# PX4FMUv2_4_6_6.net
KiCad netlist of a schematic drawn in Altium Designer
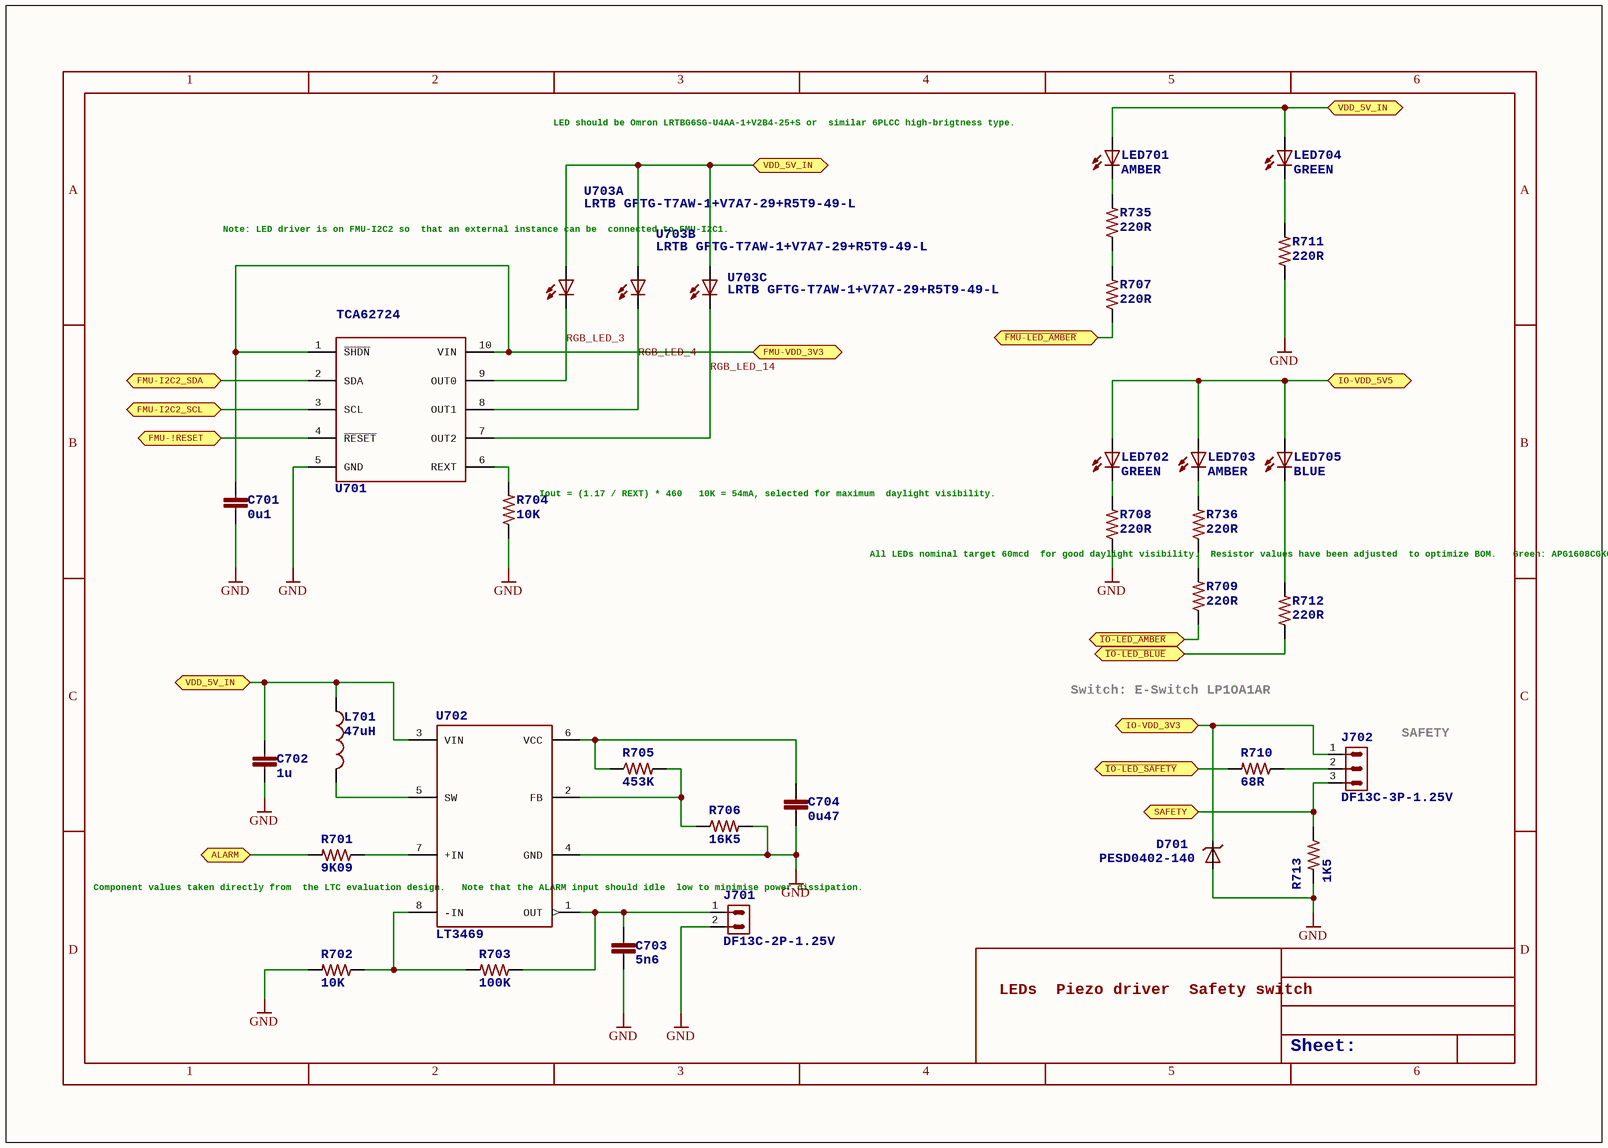
[diagram p0: PX4FMUv2.4.6_6.SchDoc]

(export (version "E")
  (design (tool "Eeschema 10.0.6"))
  (components
    (comp (ref "C701")
      (value "0u1")
      (footprint "0402-CAP")
      (description "CapacitorStandard 0603 ceramic capacitor, and 0.1\" leaded capacitor.")
      (fields (field (name "PARTNO") "CC0402ZRY5V7BB104"))
      (libsource (lib "pixhawk2") (part "CAP0402"))
    )
    (comp (ref "C702")
      (value "1u")
      (footprint "0603-CAP")
      (description "CapacitorStandard 0603 ceramic capacitor, and 0.1\" leaded capacitor.")
      (fields (field (name "PARTNO") "CC0603ZRY5V7BB105"))
      (libsource (lib "pixhawk2") (part "CAP0603"))
    )
    (comp (ref "C703")
      (value "5n6")
      (footprint "0402-CAP")
      (description "CapacitorStandard 0603 ceramic capacitor, and 0.1\" leaded capacitor.")
      (fields (field (name "PARTNO") "C0402C562K5RACTU"))
      (libsource (lib "pixhawk2") (part "CAP0402"))
    )
    (comp (ref "C704")
      (value "0u47")
      (footprint "0402-CAP")
      (description "CapacitorStandard 0603 ceramic capacitor, and 0.1\" leaded capacitor.")
      (fields (field (name "PARTNO") "C1005X5R1C474K050BC"))
      (libsource (lib "pixhawk2") (part "CAP0402"))
    )
    (comp (ref "D701")
      (value "PESD0402-140")
      (footprint "0402-TVS")
      (libsource (lib "pixhawk2") (part "DIODE-TVS"))
    )
    (comp (ref "J701")
      (value "DF13C-2P-1.25V")
      (footprint "DF13C-2P-1.25V")
      (description "DF13-2P 1.25mm Pitch Miniature Crimping Connector.")
      (fields (field (name "PARTNO") "DF13C-2P-1.25V(20)"))
      (libsource (lib "con-hirose-df13") (part "DF13-2P-1.25V"))
    )
    (comp (ref "J702")
      (value "DF13C-3P-1.25V")
      (footprint "DF13C-3P-1.25V")
      (description "DF13-3P 1.25mm Pitch Miniature Crimping Connector.")
      (fields (field (name "PARTNO") "DF13C-3P-1.25V(20)"))
      (libsource (lib "con-hirose-df13") (part "DF13-3P-1.25V"))
    )
    (comp (ref "L701")
      (value "47uH")
      (footprint "0805-IND")
      (fields (field (name "PARTNO") "MLZ2012M470W"))
      (libsource (lib "pixhawk2") (part "INDUCTOR0805"))
    )
    (comp (ref "LED701")
      (value "AMBER")
      (footprint "0603-LED")
      (fields (field (name "PARTNO") "APTD1608SECK"))
      (libsource (lib "pixhawk2") (part "LED0603"))
    )
    (comp (ref "LED702")
      (value "GREEN")
      (footprint "0603-LED")
      (fields (field (name "PARTNO") "APTD1608CGCK"))
      (libsource (lib "pixhawk2") (part "LED0603"))
    )
    (comp (ref "LED703")
      (value "AMBER")
      (footprint "0603-LED")
      (fields (field (name "PARTNO") "APTD1608SECK"))
      (libsource (lib "pixhawk2") (part "LED0603"))
    )
    (comp (ref "LED704")
      (value "GREEN")
      (footprint "0603-LED")
      (fields (field (name "PARTNO") "APTD1608CGCK"))
      (libsource (lib "pixhawk2") (part "LED0603"))
    )
    (comp (ref "LED705")
      (value "BLUE")
      (footprint "0603-LED")
      (fields (field (name "PARTNO") "APTD1608QBC/D"))
      (libsource (lib "pixhawk2") (part "LED0603"))
    )
    (comp (ref "R701")
      (value "9K09")
      (footprint "0402-RES")
      (fields (field (name "PARTNO") "RMCF0402FT9K09"))
      (libsource (lib "pixhawk2") (part "RESISTOR0402-RES"))
    )
    (comp (ref "R702")
      (value "10K")
      (footprint "0402-RES")
      (fields (field (name "PARTNO") "RC0402FR-0710KL"))
      (libsource (lib "pixhawk2") (part "RESISTOR0402-RES"))
    )
    (comp (ref "R703")
      (value "100K")
      (footprint "0402-RES")
      (fields (field (name "PARTNO") "RC0402FR-07100KL"))
      (libsource (lib "pixhawk2") (part "RESISTOR0402-RES"))
    )
    (comp (ref "R704")
      (value "10K")
      (footprint "0402-RES")
      (fields (field (name "PARTNO") "RC0402FR-0710KL"))
      (libsource (lib "pixhawk2") (part "RESISTOR0402-RES"))
    )
    (comp (ref "R705")
      (value "453K")
      (footprint "0402-RES")
      (fields (field (name "PARTNO") "RMCF0402FT453K"))
      (libsource (lib "pixhawk2") (part "RESISTOR0402-RES"))
    )
    (comp (ref "R706")
      (value "16K5")
      (footprint "0402-RES")
      (fields (field (name "PARTNO") "RMCF0402FT16K5"))
      (libsource (lib "pixhawk2") (part "RESISTOR0402-RES"))
    )
    (comp (ref "R707")
      (value "220R")
      (footprint "0402-RES")
      (fields (field (name "PARTNO") "RC0402FR-07220RL"))
      (libsource (lib "pixhawk2") (part "RESISTOR0402-RES"))
    )
    (comp (ref "R708")
      (value "220R")
      (footprint "0402-RES")
      (fields (field (name "PARTNO") "RC0402FR-07220RL"))
      (libsource (lib "pixhawk2") (part "RESISTOR0402-RES"))
    )
    (comp (ref "R709")
      (value "220R")
      (footprint "0402-RES")
      (fields (field (name "PARTNO") "RC0402FR-07220RL"))
      (libsource (lib "pixhawk2") (part "RESISTOR0402-RES"))
    )
    (comp (ref "R710")
      (value "68R")
      (footprint "0402-RES")
      (fields (field (name "PARTNO") "ERJ-2GEJ680X"))
      (libsource (lib "pixhawk2") (part "RESISTOR0402-RES"))
    )
    (comp (ref "R711")
      (value "220R")
      (footprint "0402-RES")
      (fields (field (name "PARTNO") "RC0402FR-07220RL"))
      (libsource (lib "pixhawk2") (part "RESISTOR0402-RES"))
    )
    (comp (ref "R712")
      (value "220R")
      (footprint "0402-RES")
      (fields (field (name "PARTNO") "RC0402FR-07220RL"))
      (libsource (lib "pixhawk2") (part "RESISTOR0402-RES"))
    )
    (comp (ref "R713")
      (value "1K5")
      (footprint "0402-RES")
      (libsource (lib "pixhawk2") (part "RESISTOR0402-RES"))
    )
    (comp (ref "R735")
      (value "220R")
      (footprint "0402-RES")
      (fields (field (name "PARTNO") "RC0402FR-07220RL"))
      (libsource (lib "pixhawk2") (part "RESISTOR0402-RES"))
    )
    (comp (ref "R736")
      (value "220R")
      (footprint "0402-RES")
      (fields (field (name "PARTNO") "RC0402FR-07220RL"))
      (libsource (lib "pixhawk2") (part "RESISTOR0402-RES"))
    )
    (comp (ref "U701")
      (value "TCA62724FMG")
      (footprint "SON10")
      (description "Toshiba TCA62724FMG I2C RGB LED driver")
      (fields (field (name "TCA62724") "TCA62724"))
      (libsource (lib "pixhawk2") (part "TCA62724FMG"))
    )
    (comp (ref "U702")
      (value "LT3469")
      (footprint "SOT23-8")
      (description "LT3469 Piezo microactuator driver with boost regulator")
      (fields (field (name "PARTNO") "LT3469ETS8"))
      (libsource (lib "pixhawk2") (part "LT3469"))
    )
    (comp (ref "U703")
      (value "LRTB GFTG-T7AW-1+V7A7-29+R5T9-49-L")
      (footprint "6-PLCC")
      (description "RGB LED with separate anode/cathode terminals")
      (libsource (lib "pixhawk2") (part "RGB-LED6-PLCC"))
    )
  )
  (nets
    (net (code "1") (name "/ALARM") (class "Default")
      (node (ref "R701") (pin "P$2") (pinfunction "2_P$2") (pintype "passive"))
    )
    (net (code "2") (name "/FMU-!RESET") (class "Default")
      (node (ref "U701") (pin "4") (pinfunction "~{RESET}_4") (pintype "passive"))
    )
    (net (code "3") (name "/FMU-I2C2_SCL") (class "Default")
      (node (ref "U701") (pin "3") (pinfunction "SCL_3") (pintype "passive"))
    )
    (net (code "4") (name "/FMU-I2C2_SDA") (class "Default")
      (node (ref "U701") (pin "2") (pinfunction "SDA_2") (pintype "passive"))
    )
    (net (code "5") (name "/FMU-VDD_3V3") (class "Default")
      (node (ref "C701") (pin "P$1") (pinfunction "1_P$1") (pintype "passive"))
      (node (ref "U701") (pin "1") (pinfunction "~{SHDN}_1") (pintype "passive"))
      (node (ref "U701") (pin "10") (pinfunction "VIN_10") (pintype "power_in"))
    )
    (net (code "6") (name "/IO-VDD_3V3") (class "Default")
      (node (ref "D701") (pin "C") (pinfunction "C_C") (pintype "passive"))
      (node (ref "J702") (pin "1") (pinfunction "1_1") (pintype "passive"))
    )
    (net (code "7") (name "/IO-VDD_5V5") (class "Default")
      (node (ref "LED702") (pin "A") (pinfunction "A_A") (pintype "passive"))
      (node (ref "LED703") (pin "A") (pinfunction "A_A") (pintype "passive"))
      (node (ref "LED705") (pin "A") (pinfunction "A_A") (pintype "passive"))
    )
    (net (code "8") (name "/RGB_LED_3") (class "Default")
      (node (ref "U701") (pin "9") (pinfunction "OUT0_9") (pintype "open_collector"))
      (node (ref "U703") (pin "C1") (pinfunction "C_C1") (pintype "passive"))
    )
    (net (code "9") (name "/RGB_LED_4") (class "Default")
      (node (ref "U701") (pin "8") (pinfunction "OUT1_8") (pintype "open_collector"))
      (node (ref "U703") (pin "C2") (pinfunction "C_C2") (pintype "passive"))
    )
    (net (code "10") (name "/RGB_LED_14") (class "Default")
      (node (ref "U701") (pin "7") (pinfunction "OUT2_7") (pintype "open_collector"))
      (node (ref "U703") (pin "C3") (pinfunction "C_C3") (pintype "passive"))
    )
    (net (code "11") (name "/SAFETY") (class "Default")
      (node (ref "J702") (pin "3") (pinfunction "3_3") (pintype "passive"))
      (node (ref "R713") (pin "P$1") (pinfunction "1_P$1") (pintype "passive"))
    )
    (net (code "12") (name "/VDD_5V_IN") (class "Default")
      (node (ref "C702") (pin "P$1") (pinfunction "1_P$1") (pintype "passive"))
      (node (ref "L701") (pin "P$1") (pinfunction "1_P$1") (pintype "passive"))
      (node (ref "LED701") (pin "A") (pinfunction "A_A") (pintype "passive"))
      (node (ref "LED704") (pin "A") (pinfunction "A_A") (pintype "passive"))
      (node (ref "U702") (pin "3") (pinfunction "VIN_3") (pintype "power_in"))
      (node (ref "U703") (pin "A1") (pinfunction "A_A1") (pintype "passive"))
      (node (ref "U703") (pin "A2") (pinfunction "A_A2") (pintype "passive"))
      (node (ref "U703") (pin "A3") (pinfunction "A_A3") (pintype "passive"))
    )
    (net (code "13") (name "/~{FMU-LED_AMBER}") (class "Default")
      (node (ref "R707") (pin "P$1") (pinfunction "1_P$1") (pintype "passive"))
    )
    (net (code "14") (name "/~{IO-LED_AMBER}") (class "Default")
      (node (ref "R709") (pin "P$1") (pinfunction "1_P$1") (pintype "passive"))
    )
    (net (code "15") (name "/~{IO-LED_BLUE}") (class "Default")
      (node (ref "R712") (pin "P$1") (pinfunction "1_P$1") (pintype "passive"))
    )
    (net (code "16") (name "/~{IO-LED_SAFETY}") (class "Default")
      (node (ref "R710") (pin "P$2") (pinfunction "2_P$2") (pintype "passive"))
    )
    (net (code "17") (name "GND") (class "Default")
      (node (ref "C701") (pin "P$2") (pinfunction "2_P$2") (pintype "passive"))
      (node (ref "C702") (pin "P$2") (pinfunction "2_P$2") (pintype "passive"))
      (node (ref "C703") (pin "P$2") (pinfunction "2_P$2") (pintype "passive"))
      (node (ref "C704") (pin "P$2") (pinfunction "2_P$2") (pintype "passive"))
      (node (ref "D701") (pin "A") (pinfunction "A_A") (pintype "passive"))
      (node (ref "J701") (pin "2") (pinfunction "2_2") (pintype "passive"))
      (node (ref "R702") (pin "P$2") (pinfunction "2_P$2") (pintype "passive"))
      (node (ref "R704") (pin "P$1") (pinfunction "1_P$1") (pintype "passive"))
      (node (ref "R706") (pin "P$2") (pinfunction "2_P$2") (pintype "passive"))
      (node (ref "R708") (pin "P$1") (pinfunction "1_P$1") (pintype "passive"))
      (node (ref "R711") (pin "P$1") (pinfunction "1_P$1") (pintype "passive"))
      (node (ref "R713") (pin "P$2") (pinfunction "2_P$2") (pintype "passive"))
      (node (ref "U701") (pin "5") (pinfunction "GND_5") (pintype "power_in"))
      (node (ref "U702") (pin "4") (pinfunction "GND_4") (pintype "power_in"))
    )
    (net (code "18") (name "Net-(C703-1)") (class "Default")
      (node (ref "C703") (pin "P$1") (pinfunction "1_P$1") (pintype "passive"))
      (node (ref "J701") (pin "1") (pinfunction "1_1") (pintype "passive"))
      (node (ref "R703") (pin "P$1") (pinfunction "1_P$1") (pintype "passive"))
      (node (ref "U702") (pin "1") (pinfunction "OUT_1") (pintype "output"))
    )
    (net (code "19") (name "Net-(C704-1)") (class "Default")
      (node (ref "C704") (pin "P$1") (pinfunction "1_P$1") (pintype "passive"))
      (node (ref "R705") (pin "P$1") (pinfunction "1_P$1") (pintype "passive"))
      (node (ref "U702") (pin "6") (pinfunction "VCC_6") (pintype "passive"))
    )
    (net (code "20") (name "Net-(L701-2)") (class "Default")
      (node (ref "L701") (pin "P$2") (pinfunction "2_P$2") (pintype "passive"))
      (node (ref "U702") (pin "5") (pinfunction "SW_5") (pintype "passive"))
    )
    (net (code "21") (name "Net-(R701-1)") (class "Default")
      (node (ref "R701") (pin "P$1") (pinfunction "1_P$1") (pintype "passive"))
      (node (ref "U702") (pin "7") (pinfunction "+IN_7") (pintype "passive"))
    )
    (net (code "22") (name "Net-(R702-1)") (class "Default")
      (node (ref "R702") (pin "P$1") (pinfunction "1_P$1") (pintype "passive"))
      (node (ref "R703") (pin "P$2") (pinfunction "2_P$2") (pintype "passive"))
      (node (ref "U702") (pin "8") (pinfunction "-IN_8") (pintype "passive"))
    )
    (net (code "23") (name "Net-(R704-2)") (class "Default")
      (node (ref "R704") (pin "P$2") (pinfunction "2_P$2") (pintype "passive"))
      (node (ref "U701") (pin "6") (pinfunction "REXT_6") (pintype "passive"))
    )
    (net (code "24") (name "Net-(R705-2)") (class "Default")
      (node (ref "R705") (pin "P$2") (pinfunction "2_P$2") (pintype "passive"))
      (node (ref "R706") (pin "P$1") (pinfunction "1_P$1") (pintype "passive"))
      (node (ref "U702") (pin "2") (pinfunction "FB_2") (pintype "passive"))
    )
    (net (code "25") (name "Net-(R707-2)") (class "Default")
      (node (ref "R707") (pin "P$2") (pinfunction "2_P$2") (pintype "passive"))
      (node (ref "R735") (pin "P$1") (pinfunction "1_P$1") (pintype "passive"))
    )
    (net (code "26") (name "Net-(R708-2)") (class "Default")
      (node (ref "LED702") (pin "C") (pinfunction "C_C") (pintype "passive"))
      (node (ref "R708") (pin "P$2") (pinfunction "2_P$2") (pintype "passive"))
    )
    (net (code "27") (name "Net-(R709-2)") (class "Default")
      (node (ref "R709") (pin "P$2") (pinfunction "2_P$2") (pintype "passive"))
      (node (ref "R736") (pin "P$1") (pinfunction "1_P$1") (pintype "passive"))
    )
    (net (code "28") (name "Net-(R710-1)") (class "Default")
      (node (ref "J702") (pin "2") (pinfunction "2_2") (pintype "passive"))
      (node (ref "R710") (pin "P$1") (pinfunction "1_P$1") (pintype "passive"))
    )
    (net (code "29") (name "Net-(R711-2)") (class "Default")
      (node (ref "LED704") (pin "C") (pinfunction "C_C") (pintype "passive"))
      (node (ref "R711") (pin "P$2") (pinfunction "2_P$2") (pintype "passive"))
    )
    (net (code "30") (name "Net-(R712-2)") (class "Default")
      (node (ref "LED705") (pin "C") (pinfunction "C_C") (pintype "passive"))
      (node (ref "R712") (pin "P$2") (pinfunction "2_P$2") (pintype "passive"))
    )
    (net (code "31") (name "Net-(R735-2)") (class "Default")
      (node (ref "LED701") (pin "C") (pinfunction "C_C") (pintype "passive"))
      (node (ref "R735") (pin "P$2") (pinfunction "2_P$2") (pintype "passive"))
    )
    (net (code "32") (name "Net-(R736-2)") (class "Default")
      (node (ref "LED703") (pin "C") (pinfunction "C_C") (pintype "passive"))
      (node (ref "R736") (pin "P$2") (pinfunction "2_P$2") (pintype "passive"))
    )
  )
)
